# daclock-2_0.net
KiCad netlist of a schematic drawn in EAGLE
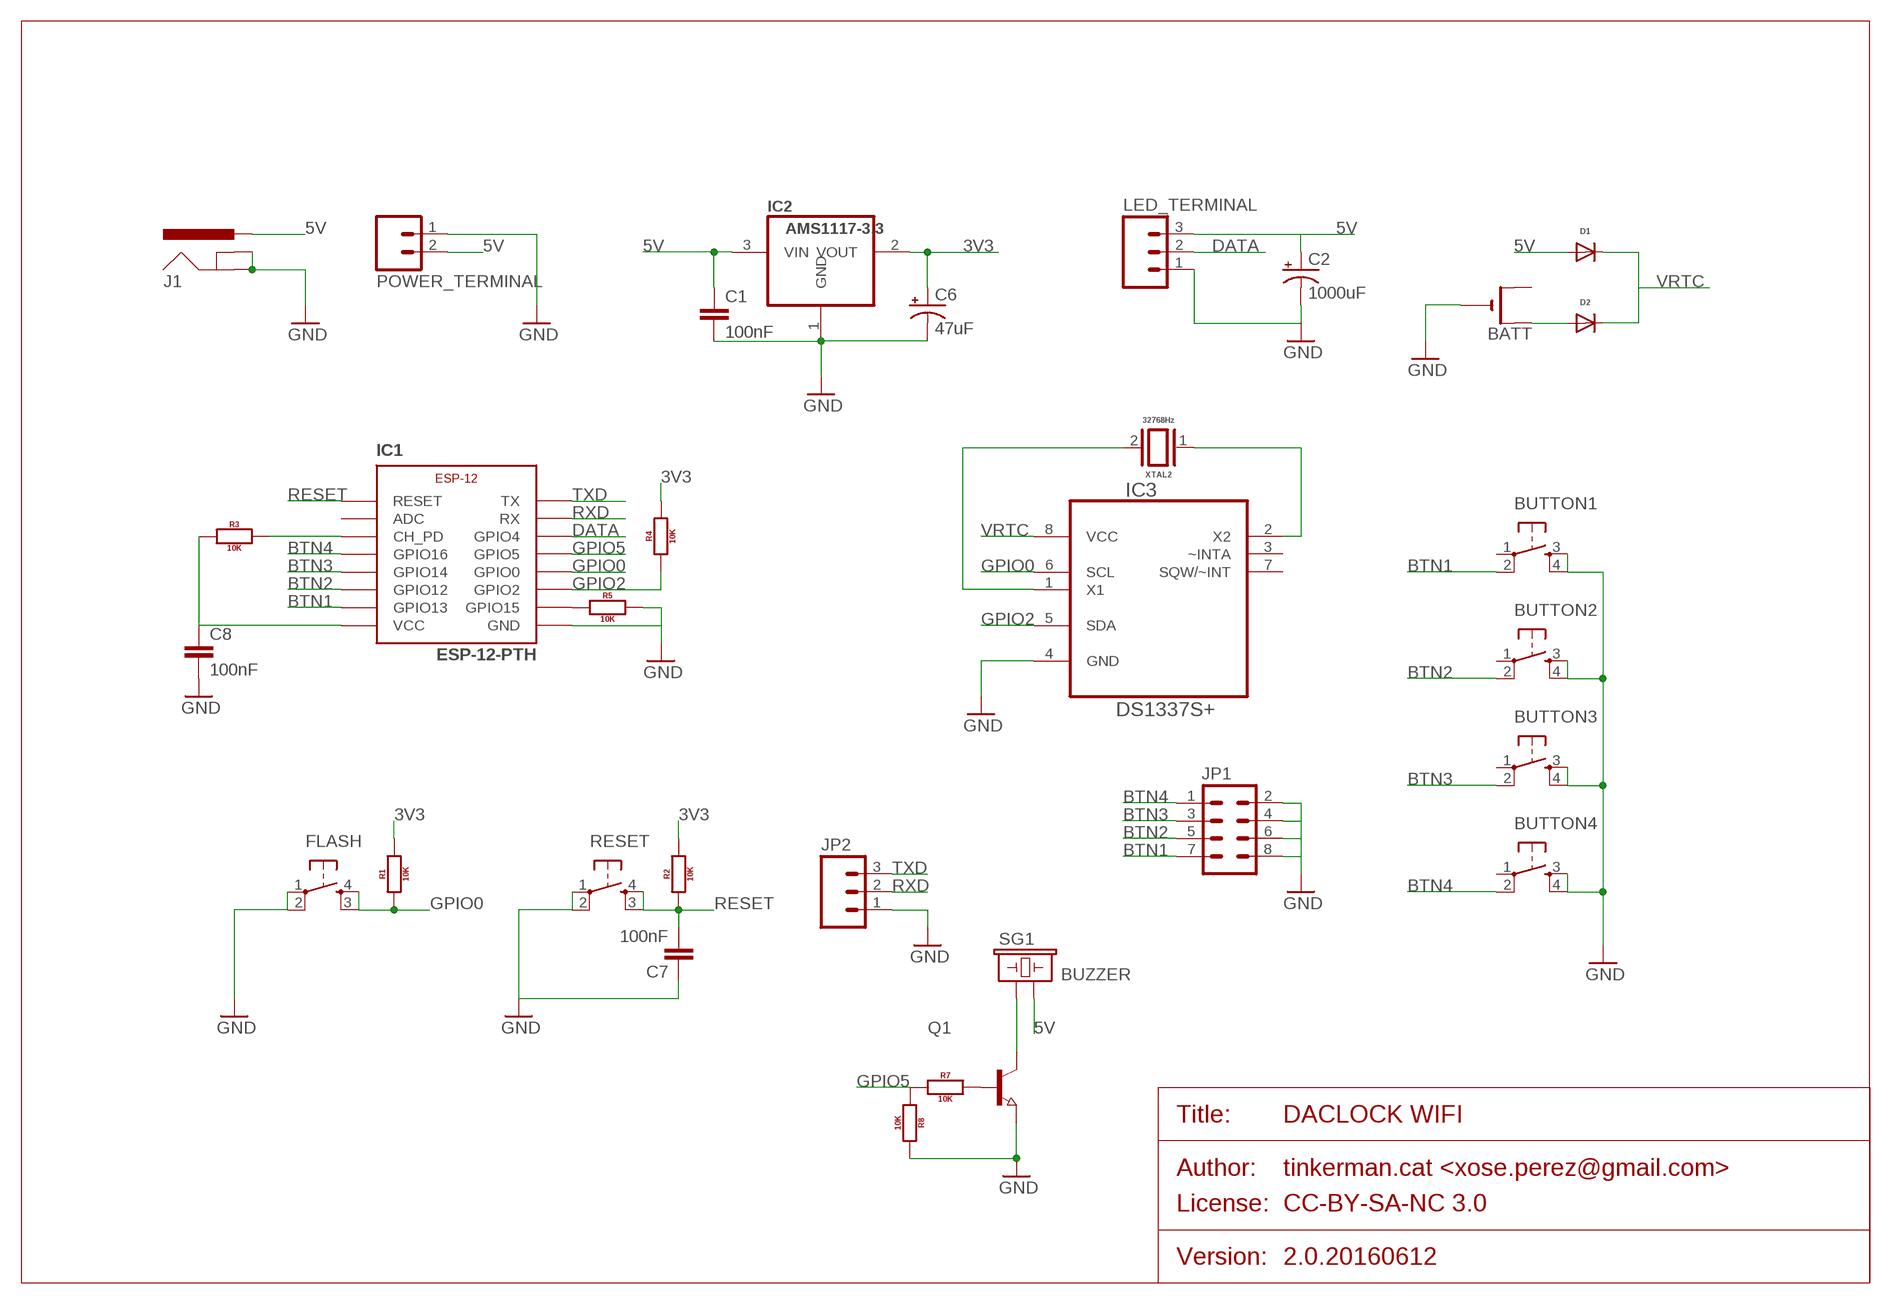
[diagram p0: schematic, sheet 1]

(export (version "E")
  (design (tool "Eeschema 10.0.6"))
  (components
    (comp (ref "BATT")
      (value "CR2032SMT")
      (footprint "eagle-import:CR2032-SMD")
      (libsource (lib "eagle-import") (part "CR2032SMT"))
    )
    (comp (ref "BUTTON1")
      (value "BTN1")
      (footprint "eagle-import:TACTILE-BUTTON")
      (libsource (lib "eagle-import") (part "TACTILE_BUTTON_PTH"))
    )
    (comp (ref "BUTTON2")
      (value "BTN2")
      (footprint "eagle-import:TACTILE-BUTTON")
      (libsource (lib "eagle-import") (part "TACTILE_BUTTON_PTH"))
    )
    (comp (ref "BUTTON3")
      (value "BTN3")
      (footprint "eagle-import:TACTILE-BUTTON")
      (libsource (lib "eagle-import") (part "TACTILE_BUTTON_PTH"))
    )
    (comp (ref "BUTTON4")
      (value "BTN4")
      (footprint "eagle-import:TACTILE-BUTTON")
      (libsource (lib "eagle-import") (part "TACTILE_BUTTON_PTH"))
    )
    (comp (ref "C1")
      (value "100nF")
      (footprint "eagle-import:0805")
      (libsource (lib "eagle-import") (part "C-EU0805"))
    )
    (comp (ref "C2")
      (value "1000uF")
      (footprint "eagle-import:PANASONIC_G")
      (libsource (lib "eagle-import") (part "CAP_POLG"))
    )
    (comp (ref "C6")
      (value "47uF")
      (footprint "eagle-import:PANASONIC_C")
      (libsource (lib "eagle-import") (part "CAP_POLC"))
    )
    (comp (ref "C7")
      (value "100nF")
      (footprint "eagle-import:0805")
      (libsource (lib "eagle-import") (part "C-EU0805"))
    )
    (comp (ref "C8")
      (value "100nF")
      (footprint "eagle-import:0805")
      (libsource (lib "eagle-import") (part "C-EU0805"))
    )
    (comp (ref "D1")
      (value "DIODE-SMD")
      (footprint "eagle-import:0805_DIODE")
      (libsource (lib "eagle-import") (part "DIODE-SMD"))
    )
    (comp (ref "D2")
      (value "DIODE-SMD")
      (footprint "eagle-import:0805_DIODE")
      (libsource (lib "eagle-import") (part "DIODE-SMD"))
    )
    (comp (ref "FLASH")
      (value "TACTILE_BUTTON_SMD")
      (footprint "eagle-import:TACTILE-BUTTON-SMD")
      (libsource (lib "eagle-import") (part "TACTILE_BUTTON_SMD"))
    )
    (comp (ref "IC1")
      (value "ESP-12-PTH")
      (footprint "eagle-import:ESP-12-PTH")
      (libsource (lib "eagle-import") (part "ESP-12-PTH"))
    )
    (comp (ref "IC2")
      (value "AMS1117-3.3")
      (footprint "eagle-import:SOT223")
      (fields (field (name "MPN") "REG1117"))
      (libsource (lib "eagle-import") (part "REG1117"))
    )
    (comp (ref "IC3")
      (value "DS1337S+")
      (footprint "eagle-import:SOIC127P600X175-8N")
      (libsource (lib "eagle-import") (part "DS1337S+"))
    )
    (comp (ref "J1")
      (value "POWER_JACKPTH")
      (footprint "eagle-import:POWER_JACK_PTH")
      (libsource (lib "eagle-import") (part "POWER_JACKPTH"))
    )
    (comp (ref "JP1")
      (value "M04X2")
      (footprint "eagle-import:2X4")
      (libsource (lib "eagle-import") (part "M04X2"))
    )
    (comp (ref "JP2")
      (value "M03PTH")
      (footprint "eagle-import:1X03")
      (libsource (lib "eagle-import") (part "M03PTH"))
    )
    (comp (ref "LED_TERMINAL")
      (value "M03200MIL")
      (footprint "eagle-import:SCREWTERMINAL-200MIL-3")
      (libsource (lib "eagle-import") (part "M03200MIL"))
    )
    (comp (ref "POWER_TERMINAL")
      (value "M02200MIL")
      (footprint "eagle-import:SCREWTERMINAL-200MIL-2")
      (libsource (lib "eagle-import") (part "M02200MIL"))
    )
    (comp (ref "Q1")
      (value "NPN-TRANSISTOR_SOT23")
      (footprint "eagle-import:SOT23")
      (libsource (lib "eagle-import") (part "NPN-TRANSISTOR_SOT23"))
    )
    (comp (ref "R1")
      (value "10K")
      (footprint "eagle-import:0805")
      (libsource (lib "eagle-import") (part "RESISTOR0805"))
    )
    (comp (ref "R2")
      (value "10K")
      (footprint "eagle-import:0805")
      (libsource (lib "eagle-import") (part "RESISTOR0805"))
    )
    (comp (ref "R3")
      (value "10K")
      (footprint "eagle-import:0805")
      (libsource (lib "eagle-import") (part "RESISTOR0805"))
    )
    (comp (ref "R4")
      (value "10K")
      (footprint "eagle-import:0805")
      (libsource (lib "eagle-import") (part "RESISTOR0805"))
    )
    (comp (ref "R5")
      (value "10K")
      (footprint "eagle-import:0805")
      (libsource (lib "eagle-import") (part "RESISTOR0805"))
    )
    (comp (ref "R7")
      (value "10K")
      (footprint "eagle-import:0805")
      (libsource (lib "eagle-import") (part "RESISTOR0805"))
    )
    (comp (ref "R8")
      (value "10K")
      (footprint "eagle-import:0805")
      (libsource (lib "eagle-import") (part "RESISTOR0805"))
    )
    (comp (ref "RESET")
      (value "TACTILE_BUTTON_SMD")
      (footprint "eagle-import:TACTILE-BUTTON-SMD")
      (libsource (lib "eagle-import") (part "TACTILE_BUTTON_SMD"))
    )
    (comp (ref "SG1")
      (value "BUZZER")
      (footprint "eagle-import:BUZZER-12MM")
      (libsource (lib "eagle-import") (part "BUZZERPTH"))
    )
    (comp (ref "XTAL2")
      (value "32768Hz")
      (footprint "eagle-import:TC38H")
      (libsource (lib "eagle-import") (part "CRYSTAL_TC38H"))
    )
  )
  (nets
    (net (code "1") (name "/3V3") (class "Default")
      (node (ref "C6") (pin "+") (pinfunction "+_+") (pintype "passive"))
      (node (ref "C8") (pin "1") (pinfunction "1_1") (pintype "passive"))
      (node (ref "IC1") (pin "VCC") (pinfunction "VCC_VCC") (pintype "bidirectional"))
      (node (ref "IC2") (pin "2") (pinfunction "VOUT_2") (pintype "output"))
      (node (ref "R1") (pin "2") (pinfunction "2_2") (pintype "passive"))
      (node (ref "R2") (pin "2") (pinfunction "2_2") (pintype "passive"))
      (node (ref "R3") (pin "1") (pinfunction "1_1") (pintype "passive"))
      (node (ref "R4") (pin "2") (pinfunction "2_2") (pintype "passive"))
    )
    (net (code "2") (name "/5V") (class "Default")
      (node (ref "C1") (pin "1") (pinfunction "1_1") (pintype "passive"))
      (node (ref "C2") (pin "+") (pinfunction "+_+") (pintype "passive"))
      (node (ref "D1") (pin "A") (pinfunction "A_A") (pintype "passive"))
      (node (ref "IC2") (pin "3") (pinfunction "VIN_3") (pintype "input"))
      (node (ref "J1") (pin "PWR") (pinfunction "PWR_PWR") (pintype "bidirectional"))
      (node (ref "LED_TERMINAL") (pin "3") (pinfunction "3_3") (pintype "passive"))
      (node (ref "POWER_TERMINAL") (pin "2") (pinfunction "2_2") (pintype "passive"))
      (node (ref "SG1") (pin "-") (pinfunction "2_-") (pintype "passive"))
    )
    (net (code "3") (name "/BTN1") (class "Default")
      (node (ref "BUTTON1") (pin "2") (pinfunction "SWB1_2") (pintype "passive"))
      (node (ref "IC1") (pin "GPIO13") (pinfunction "GPIO13_GPIO13") (pintype "bidirectional"))
      (node (ref "JP1") (pin "7") (pinfunction "7_7") (pintype "passive"))
    )
    (net (code "4") (name "/BTN2") (class "Default")
      (node (ref "BUTTON2") (pin "2") (pinfunction "SWB1_2") (pintype "passive"))
      (node (ref "IC1") (pin "GPIO12") (pinfunction "GPIO12_GPIO12") (pintype "bidirectional"))
      (node (ref "JP1") (pin "5") (pinfunction "5_5") (pintype "passive"))
    )
    (net (code "5") (name "/BTN3") (class "Default")
      (node (ref "BUTTON3") (pin "2") (pinfunction "SWB1_2") (pintype "passive"))
      (node (ref "IC1") (pin "GPIO14") (pinfunction "GPIO14_GPIO14") (pintype "bidirectional"))
      (node (ref "JP1") (pin "3") (pinfunction "3_3") (pintype "passive"))
    )
    (net (code "6") (name "/BTN4") (class "Default")
      (node (ref "BUTTON4") (pin "2") (pinfunction "SWB1_2") (pintype "passive"))
      (node (ref "IC1") (pin "GPIO16") (pinfunction "GPIO16_GPIO16") (pintype "bidirectional"))
      (node (ref "JP1") (pin "1") (pinfunction "1_1") (pintype "passive"))
    )
    (net (code "7") (name "/DATA") (class "Default")
      (node (ref "IC1") (pin "GPIO4") (pinfunction "GPIO4_GPIO4") (pintype "bidirectional"))
      (node (ref "LED_TERMINAL") (pin "2") (pinfunction "2_2") (pintype "passive"))
    )
    (net (code "8") (name "/GPIO0") (class "Default")
      (node (ref "FLASH") (pin "3") (pinfunction "SWB2_3") (pintype "passive"))
      (node (ref "FLASH") (pin "4") (pinfunction "SWA2_4") (pintype "passive"))
      (node (ref "IC1") (pin "GPIO0") (pinfunction "GPIO0_GPIO0") (pintype "bidirectional"))
      (node (ref "IC3") (pin "6") (pinfunction "SCL_6") (pintype "input"))
      (node (ref "R1") (pin "1") (pinfunction "1_1") (pintype "passive"))
    )
    (net (code "9") (name "/GPIO2") (class "Default")
      (node (ref "IC1") (pin "GPIO2") (pinfunction "GPIO2_GPIO2") (pintype "bidirectional"))
      (node (ref "IC3") (pin "5") (pinfunction "SDA_5") (pintype "bidirectional"))
      (node (ref "R4") (pin "1") (pinfunction "1_1") (pintype "passive"))
    )
    (net (code "10") (name "/GPIO5") (class "Default")
      (node (ref "IC1") (pin "GPIO5") (pinfunction "GPIO5_GPIO5") (pintype "bidirectional"))
      (node (ref "R7") (pin "1") (pinfunction "1_1") (pintype "passive"))
      (node (ref "R8") (pin "1") (pinfunction "1_1") (pintype "passive"))
    )
    (net (code "11") (name "/RESET") (class "Default")
      (node (ref "C7") (pin "2") (pinfunction "2_2") (pintype "passive"))
      (node (ref "IC1") (pin "RESET") (pinfunction "RESET_RESET") (pintype "bidirectional"))
      (node (ref "R2") (pin "1") (pinfunction "1_1") (pintype "passive"))
      (node (ref "RESET") (pin "3") (pinfunction "SWB2_3") (pintype "passive"))
      (node (ref "RESET") (pin "4") (pinfunction "SWA2_4") (pintype "passive"))
    )
    (net (code "12") (name "/RXD") (class "Default")
      (node (ref "IC1") (pin "RX") (pinfunction "RX_RX") (pintype "bidirectional"))
      (node (ref "JP2") (pin "2") (pinfunction "2_2") (pintype "passive"))
    )
    (net (code "13") (name "/TXD") (class "Default")
      (node (ref "IC1") (pin "TX") (pinfunction "TX_TX") (pintype "bidirectional"))
      (node (ref "JP2") (pin "3") (pinfunction "3_3") (pintype "passive"))
    )
    (net (code "14") (name "/VRTC") (class "Default")
      (node (ref "D1") (pin "C") (pinfunction "C_C") (pintype "passive"))
      (node (ref "D2") (pin "C") (pinfunction "C_C") (pintype "passive"))
      (node (ref "IC3") (pin "8") (pinfunction "VCC_8") (pintype "power_in"))
    )
    (net (code "15") (name "GND") (class "Default")
      (node (ref "BATT") (pin "-") (pinfunction "-_-") (pintype "passive"))
      (node (ref "BUTTON1") (pin "3") (pinfunction "SWA2_3") (pintype "passive"))
      (node (ref "BUTTON1") (pin "4") (pinfunction "SWB2_4") (pintype "passive"))
      (node (ref "BUTTON2") (pin "3") (pinfunction "SWA2_3") (pintype "passive"))
      (node (ref "BUTTON2") (pin "4") (pinfunction "SWB2_4") (pintype "passive"))
      (node (ref "BUTTON3") (pin "3") (pinfunction "SWA2_3") (pintype "passive"))
      (node (ref "BUTTON3") (pin "4") (pinfunction "SWB2_4") (pintype "passive"))
      (node (ref "BUTTON4") (pin "3") (pinfunction "SWA2_3") (pintype "passive"))
      (node (ref "BUTTON4") (pin "4") (pinfunction "SWB2_4") (pintype "passive"))
      (node (ref "C1") (pin "2") (pinfunction "2_2") (pintype "passive"))
      (node (ref "C2") (pin "-") (pinfunction "-_-") (pintype "passive"))
      (node (ref "C6") (pin "-") (pinfunction "-_-") (pintype "passive"))
      (node (ref "C7") (pin "1") (pinfunction "1_1") (pintype "passive"))
      (node (ref "C8") (pin "2") (pinfunction "2_2") (pintype "passive"))
      (node (ref "FLASH") (pin "1") (pinfunction "SWA1_1") (pintype "passive"))
      (node (ref "FLASH") (pin "2") (pinfunction "SWB1_2") (pintype "passive"))
      (node (ref "IC1") (pin "GND") (pinfunction "GND_GND") (pintype "bidirectional"))
      (node (ref "IC2") (pin "1") (pinfunction "GND_1") (pintype "power_in"))
      (node (ref "IC3") (pin "4") (pinfunction "GND_4") (pintype "passive"))
      (node (ref "J1") (pin "GND") (pinfunction "GND_GND") (pintype "bidirectional"))
      (node (ref "J1") (pin "GNDBREAK") (pinfunction "GNDBREAK_GNDBREAK") (pintype "bidirectional"))
      (node (ref "JP1") (pin "2") (pinfunction "2_2") (pintype "passive"))
      (node (ref "JP1") (pin "4") (pinfunction "4_4") (pintype "passive"))
      (node (ref "JP1") (pin "6") (pinfunction "6_6") (pintype "passive"))
      (node (ref "JP1") (pin "8") (pinfunction "8_8") (pintype "passive"))
      (node (ref "JP2") (pin "1") (pinfunction "1_1") (pintype "passive"))
      (node (ref "LED_TERMINAL") (pin "1") (pinfunction "1_1") (pintype "passive"))
      (node (ref "POWER_TERMINAL") (pin "1") (pinfunction "1_1") (pintype "passive"))
      (node (ref "Q1") (pin "2") (pinfunction "E_2") (pintype "passive"))
      (node (ref "R5") (pin "2") (pinfunction "2_2") (pintype "passive"))
      (node (ref "R8") (pin "2") (pinfunction "2_2") (pintype "passive"))
      (node (ref "RESET") (pin "1") (pinfunction "SWA1_1") (pintype "passive"))
      (node (ref "RESET") (pin "2") (pinfunction "SWB1_2") (pintype "passive"))
    )
    (net (code "16") (name "Net-(BATT-+)") (class "Default")
      (node (ref "BATT") (pin "+$1") (pinfunction "+_+$1") (pintype "passive"))
      (node (ref "D2") (pin "A") (pinfunction "A_A") (pintype "passive"))
    )
    (net (code "17") (name "Net-(IC1-PadCH_PD)") (class "Default")
      (node (ref "IC1") (pin "CH_PD") (pinfunction "CH_PD_CH_PD") (pintype "bidirectional"))
      (node (ref "R3") (pin "2") (pinfunction "2_2") (pintype "passive"))
    )
    (net (code "18") (name "Net-(IC1-PadGPIO15)") (class "Default")
      (node (ref "IC1") (pin "GPIO15") (pinfunction "GPIO15_GPIO15") (pintype "bidirectional"))
      (node (ref "R5") (pin "1") (pinfunction "1_1") (pintype "passive"))
    )
    (net (code "19") (name "Net-(IC3-X1)") (class "Default")
      (node (ref "IC3") (pin "1") (pinfunction "X1_1") (pintype "input"))
      (node (ref "XTAL2") (pin "2") (pinfunction "2_2") (pintype "passive"))
    )
    (net (code "20") (name "Net-(IC3-X2)") (class "Default")
      (node (ref "IC3") (pin "2") (pinfunction "X2_2") (pintype "passive"))
      (node (ref "XTAL2") (pin "1") (pinfunction "1_1") (pintype "passive"))
    )
    (net (code "21") (name "Net-(Q1-B)") (class "Default")
      (node (ref "Q1") (pin "1") (pinfunction "B_1") (pintype "passive"))
      (node (ref "R7") (pin "2") (pinfunction "2_2") (pintype "passive"))
    )
    (net (code "22") (name "Net-(Q1-C)") (class "Default")
      (node (ref "Q1") (pin "3") (pinfunction "C_3") (pintype "passive"))
      (node (ref "SG1") (pin "+") (pinfunction "1_+") (pintype "passive"))
    )
    (net (code "23") (name "unconnected-(BATT-+1-Pad+$2)") (class "Default")
      (node (ref "BATT") (pin "+$2") (pinfunction "+1_+$2") (pintype "passive"))
    )
    (net (code "24") (name "unconnected-(BUTTON1-SWA1-Pad1)") (class "Default")
      (node (ref "BUTTON1") (pin "1") (pinfunction "SWA1_1") (pintype "passive"))
    )
    (net (code "25") (name "unconnected-(BUTTON2-SWA1-Pad1)") (class "Default")
      (node (ref "BUTTON2") (pin "1") (pinfunction "SWA1_1") (pintype "passive"))
    )
    (net (code "26") (name "unconnected-(BUTTON3-SWA1-Pad1)") (class "Default")
      (node (ref "BUTTON3") (pin "1") (pinfunction "SWA1_1") (pintype "passive"))
    )
    (net (code "27") (name "unconnected-(BUTTON4-SWA1-Pad1)") (class "Default")
      (node (ref "BUTTON4") (pin "1") (pinfunction "SWA1_1") (pintype "passive"))
    )
    (net (code "28") (name "unconnected-(IC1-PadADC)") (class "Default")
      (node (ref "IC1") (pin "ADC") (pinfunction "ADC_ADC") (pintype "bidirectional"))
    )
    (net (code "29") (name "unconnected-(IC3-SQW{slash}~{INT}-Pad7)") (class "Default")
      (node (ref "IC3") (pin "7") (pinfunction "SQW/~{INT}_7") (pintype "output"))
    )
    (net (code "30") (name "unconnected-(IC3-~{INTA}-Pad3)") (class "Default")
      (node (ref "IC3") (pin "3") (pinfunction "~{INTA}_3") (pintype "output"))
    )
  )
)
